# SCH_NFC-Card-Rukshiya_2024-10-10.net
KiCad netlist of a schematic drawn in EasyEDA
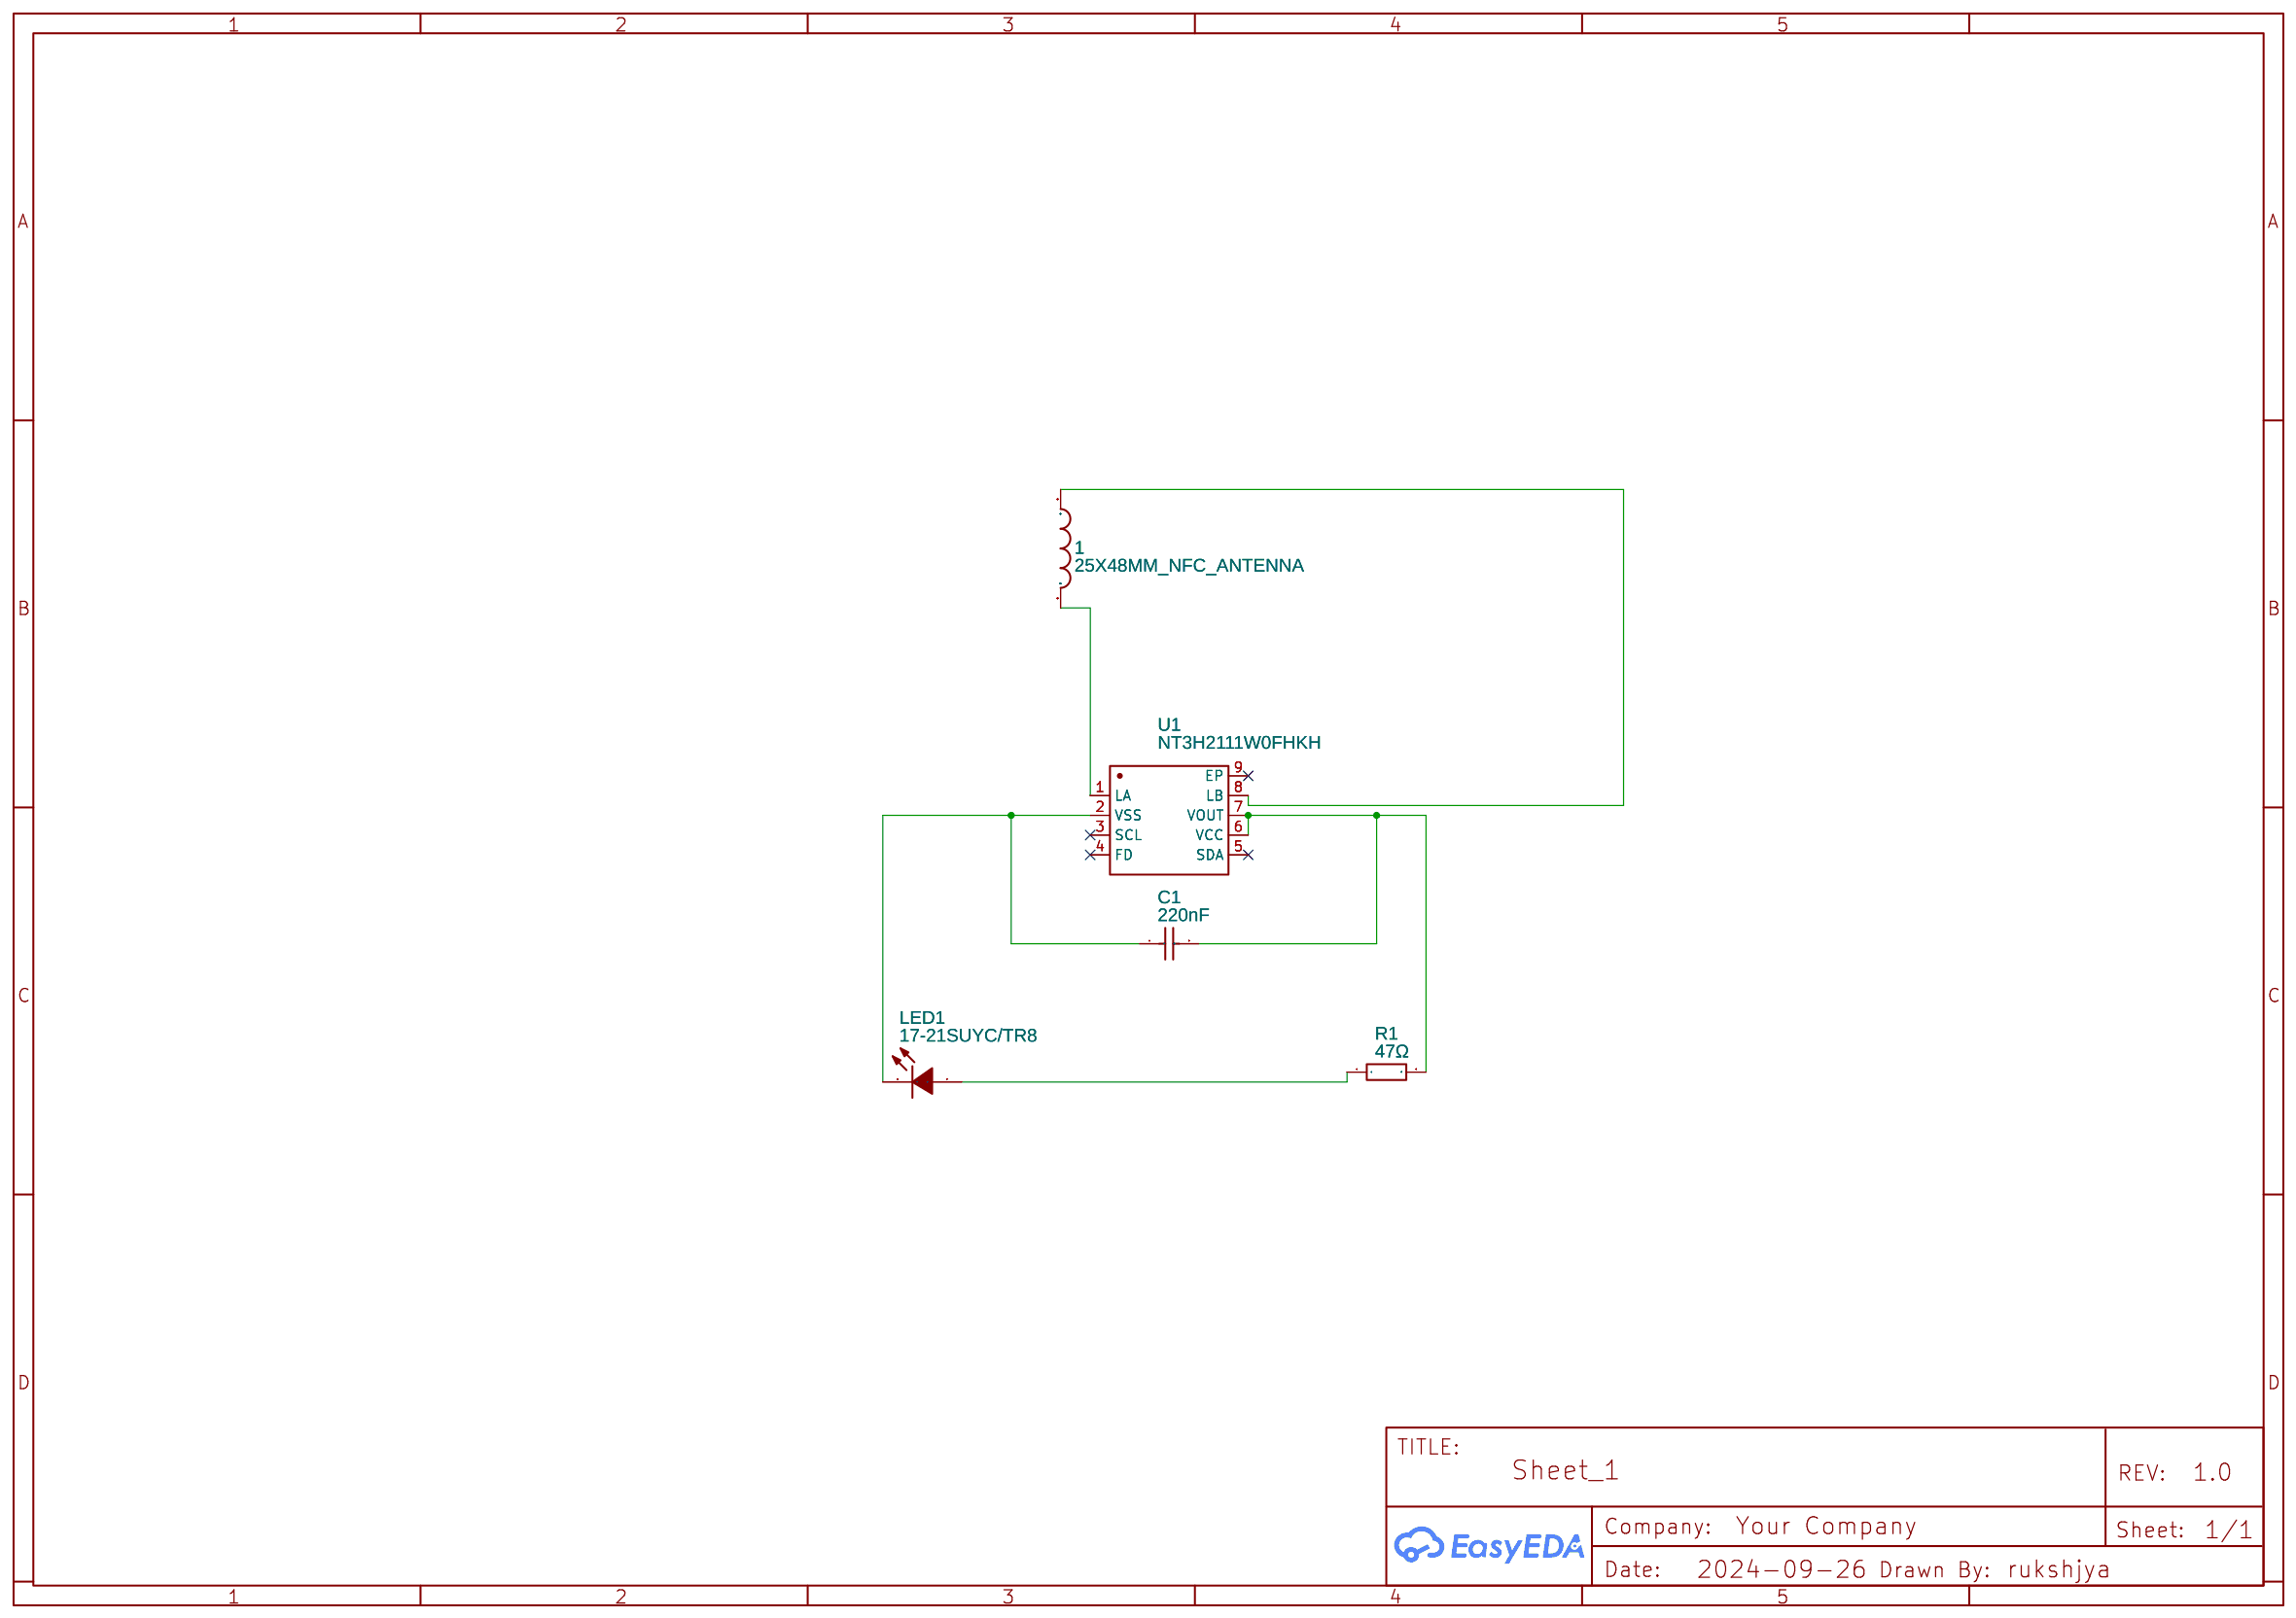
[diagram p0: schematic sheet]

(export (version "E")
  (design (tool "Eeschema 10.0.6"))
  (components
    (comp (ref "1") (value "25X48MM_NFC_ANTENNA") (libsource (lib "") (part "25X48MM_NFC_ANTENNA")))
    (comp (ref "C1")
      (value "220nF")
      (fields
        (field (name "Manufacturer Part") "CL10B224KA8NNNC")
        (field (name "Manufacturer") "SAMSUNG(三星)")
      )
      (libsource (lib "") (part "CL10B224KA8NNNC"))
    )
    (comp (ref "LED1")
      (value "17-21SUYC/TR8")
      (fields (field (name "Manufacturer Part") "KT-0805黄灯") (field (name "Manufacturer") "KENTO"))
      (libsource (lib "") (part "17-21SUYC/TR8"))
    )
    (comp (ref "R1")
      (value "47Ω")
      (fields
        (field (name "Manufacturer Part") "0603WAF470JT5E")
        (field (name "Manufacturer") "UNI-ROYAL(厚声)")
      )
      (libsource (lib "") (part "0603WAF470JT5E"))
    )
    (comp (ref "U1")
      (value "NT3H2111W0FHKH")
      (fields (field (name "Manufacturer") "NXP(恩智浦)"))
      (libsource (lib "") (part "NT3H2111W0FHKH"))
    )
  )
  (nets
    (net (code "1") (name "Net-(LED1-+)") (class "Default")
      (node (ref "LED1") (pin "1") (pinfunction "+_1") (pintype "unspecified"))
      (node (ref "R1") (pin "1") (pinfunction "1_1") (pintype "input"))
    )
    (net (code "2") (name "Net-(LED1--)") (class "Default")
      (node (ref "C1") (pin "1") (pinfunction "1_1") (pintype "input"))
      (node (ref "LED1") (pin "2") (pinfunction "-_2") (pintype "unspecified"))
      (node (ref "U1") (pin "2") (pinfunction "VSS_2") (pintype "unspecified"))
    )
    (net (code "3") (name "Net-(U1-LA)") (class "Default")
      (node (ref "1") (pin "P$2") (pinfunction "P$2_P$2") (pintype "bidirectional"))
      (node (ref "U1") (pin "1") (pinfunction "LA_1") (pintype "unspecified"))
    )
    (net (code "4") (name "Net-(U1-LB)") (class "Default")
      (node (ref "1") (pin "P$1") (pinfunction "P$1_P$1") (pintype "bidirectional"))
      (node (ref "U1") (pin "8") (pinfunction "LB_8") (pintype "unspecified"))
    )
    (net (code "5") (name "Net-(U1-VCC)") (class "Default")
      (node (ref "C1") (pin "2") (pinfunction "2_2") (pintype "input"))
      (node (ref "R1") (pin "2") (pinfunction "2_2") (pintype "input"))
      (node (ref "U1") (pin "6") (pinfunction "VCC_6") (pintype "unspecified"))
      (node (ref "U1") (pin "7") (pinfunction "VOUT_7") (pintype "unspecified"))
    )
    (net (code "6") (name "unconnected-(U1-EP-Pad9)") (class "Default")
      (node (ref "U1") (pin "9") (pinfunction "EP_9") (pintype "unspecified+no_connect"))
    )
    (net (code "7") (name "unconnected-(U1-FD-Pad4)") (class "Default")
      (node (ref "U1") (pin "4") (pinfunction "FD_4") (pintype "unspecified+no_connect"))
    )
    (net (code "8") (name "unconnected-(U1-SCL-Pad3)") (class "Default")
      (node (ref "U1") (pin "3") (pinfunction "SCL_3") (pintype "unspecified+no_connect"))
    )
    (net (code "9") (name "unconnected-(U1-SDA-Pad5)") (class "Default")
      (node (ref "U1") (pin "5") (pinfunction "SDA_5") (pintype "unspecified+no_connect"))
    )
  )
)
